# Main.net
KiCad netlist of a schematic drawn in EAGLE
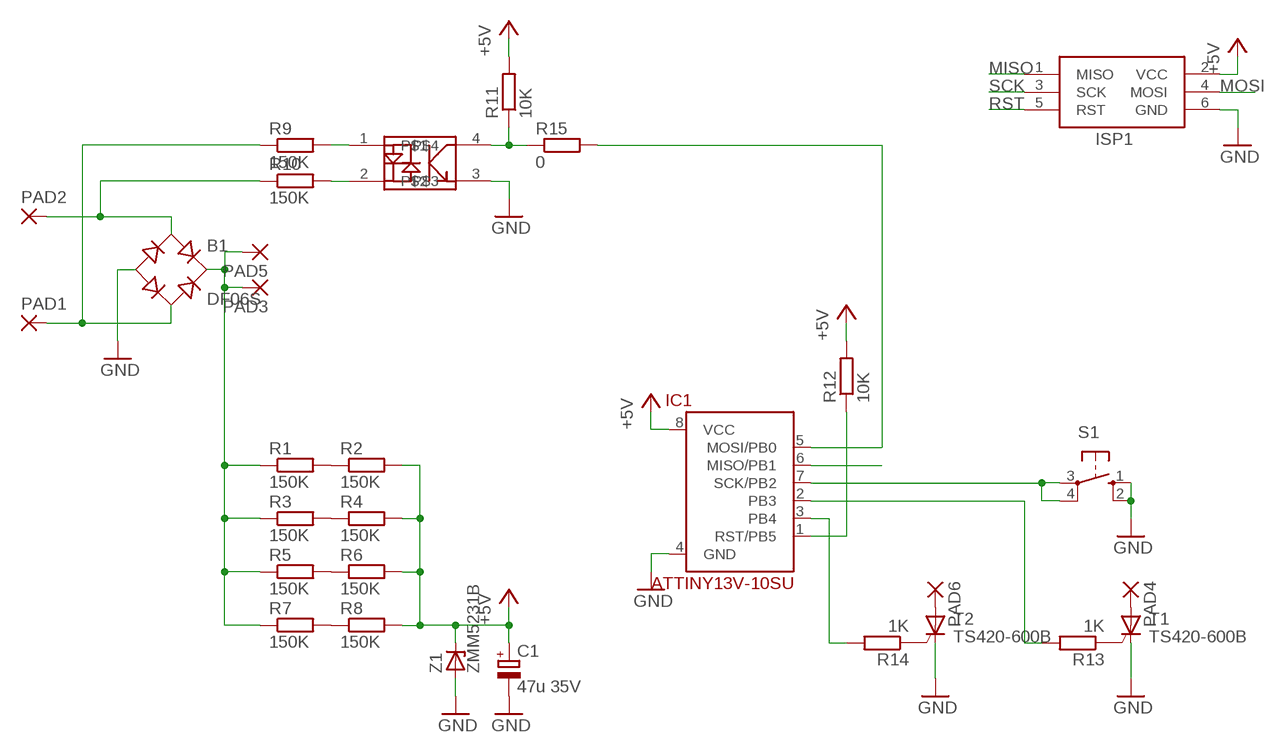
[diagram p0: schematic, sheet 1]

(export (version "E")
  (design (tool "Eeschema 10.0.6"))
  (components
    (comp (ref "B1")
      (value "DF06S")
      (footprint "eagle-import:DFS")
      (libsource (lib "eagle-import") (part "DFS06"))
    )
    (comp (ref "C1")
      (value "47u 35V")
      (footprint "eagle-import:CT7343")
      (libsource (lib "eagle-import") (part "CPOL-EUCT7343"))
    )
    (comp (ref "IC1")
      (value "ATTINY13V-10SU")
      (footprint "eagle-import:SOIC8")
      (libsource (lib "eagle-import") (part "ATTINY13V-10SU"))
    )
    (comp (ref "ISP1")
      (value "AVRISP-6")
      (footprint "eagle-import:AVRISP")
      (libsource (lib "eagle-import") (part "AVRISP-6"))
    )
    (comp (ref "PAD1")
      (value "SMD5")
      (footprint "eagle-import:SMD2,54-5,08")
      (libsource (lib "eagle-import") (part "SMD5"))
    )
    (comp (ref "PAD2")
      (value "SMD5")
      (footprint "eagle-import:SMD2,54-5,08")
      (libsource (lib "eagle-import") (part "SMD5"))
    )
    (comp (ref "PAD3")
      (value "SMD5")
      (footprint "eagle-import:SMD2,54-5,08")
      (libsource (lib "eagle-import") (part "SMD5"))
    )
    (comp (ref "PAD4")
      (value "SMD5")
      (footprint "eagle-import:SMD2,54-5,08")
      (libsource (lib "eagle-import") (part "SMD5"))
    )
    (comp (ref "PAD5")
      (value "SMD5")
      (footprint "eagle-import:SMD2,54-5,08")
      (libsource (lib "eagle-import") (part "SMD5"))
    )
    (comp (ref "PAD6")
      (value "SMD5")
      (footprint "eagle-import:SMD2,54-5,08")
      (libsource (lib "eagle-import") (part "SMD5"))
    )
    (comp (ref "R1")
      (value "150K")
      (footprint "eagle-import:R1206")
      (libsource (lib "eagle-import") (part "R_1206"))
    )
    (comp (ref "R2")
      (value "150K")
      (footprint "eagle-import:R1206")
      (libsource (lib "eagle-import") (part "R_1206"))
    )
    (comp (ref "R3")
      (value "150K")
      (footprint "eagle-import:R1206")
      (libsource (lib "eagle-import") (part "R_1206"))
    )
    (comp (ref "R4")
      (value "150K")
      (footprint "eagle-import:R1206")
      (libsource (lib "eagle-import") (part "R_1206"))
    )
    (comp (ref "R5")
      (value "150K")
      (footprint "eagle-import:R1206")
      (libsource (lib "eagle-import") (part "R_1206"))
    )
    (comp (ref "R6")
      (value "150K")
      (footprint "eagle-import:R1206")
      (libsource (lib "eagle-import") (part "R_1206"))
    )
    (comp (ref "R7")
      (value "150K")
      (footprint "eagle-import:R1206")
      (libsource (lib "eagle-import") (part "R_1206"))
    )
    (comp (ref "R8")
      (value "150K")
      (footprint "eagle-import:R1206")
      (libsource (lib "eagle-import") (part "R_1206"))
    )
    (comp (ref "R9")
      (value "150K")
      (footprint "eagle-import:R1206")
      (libsource (lib "eagle-import") (part "R_1206"))
    )
    (comp (ref "R10")
      (value "150K")
      (footprint "eagle-import:R1206")
      (libsource (lib "eagle-import") (part "R_1206"))
    )
    (comp (ref "R11")
      (value "10K")
      (footprint "eagle-import:R1206")
      (libsource (lib "eagle-import") (part "R_1206"))
    )
    (comp (ref "R12")
      (value "10K")
      (footprint "eagle-import:R1206")
      (libsource (lib "eagle-import") (part "R_1206"))
    )
    (comp (ref "R13")
      (value "1K")
      (footprint "eagle-import:R1206")
      (libsource (lib "eagle-import") (part "R_1206"))
    )
    (comp (ref "R14")
      (value "1K")
      (footprint "eagle-import:R1206")
      (libsource (lib "eagle-import") (part "R_1206"))
    )
    (comp (ref "R15")
      (value "0")
      (footprint "eagle-import:R0805")
      (libsource (lib "eagle-import") (part "R_0805"))
    )
    (comp (ref "S1")
      (value "10-XX")
      (footprint "eagle-import:B3F-10XX")
      (fields (field (name "MPN") "B3F-1000"))
      (libsource (lib "eagle-import") (part "10-XX"))
    )
    (comp (ref "T1")
      (value "TS420-600B")
      (footprint "eagle-import:DPAK")
      (libsource (lib "eagle-import") (part "THYRISTOR"))
    )
    (comp (ref "T2")
      (value "TS420-600B")
      (footprint "eagle-import:DPAK")
      (libsource (lib "eagle-import") (part "THYRISTOR"))
    )
    (comp (ref "U$1")
      (value "OPTO-EL3H4(TA)-VG")
      (footprint "eagle-import:SSOP4")
      (libsource (lib "eagle-import") (part "OPTO-EL3H4(TA)-VG"))
    )
    (comp (ref "Z1")
      (value "ZMM5231B")
      (footprint "eagle-import:MINIMELF")
      (libsource (lib "eagle-import") (part "ZENER_MINIMELF"))
    )
  )
  (nets
    (net (code "1") (name "+5V") (class "Default")
      (node (ref "C1") (pin "+") (pinfunction "+_+") (pintype "passive"))
      (node (ref "IC1") (pin "8") (pinfunction "VCC_8") (pintype "power_in"))
      (node (ref "ISP1") (pin "2") (pinfunction "VCC_2") (pintype "power_in"))
      (node (ref "R11") (pin "2") (pinfunction "2_2") (pintype "passive"))
      (node (ref "R12") (pin "2") (pinfunction "2_2") (pintype "passive"))
      (node (ref "R2") (pin "2") (pinfunction "2_2") (pintype "passive"))
      (node (ref "R4") (pin "2") (pinfunction "2_2") (pintype "passive"))
      (node (ref "R6") (pin "2") (pinfunction "2_2") (pintype "passive"))
      (node (ref "R8") (pin "2") (pinfunction "2_2") (pintype "passive"))
      (node (ref "Z1") (pin "C") (pinfunction "C_C") (pintype "passive"))
    )
    (net (code "2") (name "/MISO") (class "Default")
      (node (ref "IC1") (pin "6") (pinfunction "MISO/PB1_6") (pintype "bidirectional"))
      (node (ref "ISP1") (pin "1") (pinfunction "MISO_1") (pintype "input"))
    )
    (net (code "3") (name "/MOSI") (class "Default")
      (node (ref "IC1") (pin "5") (pinfunction "MOSI/PB0_5") (pintype "bidirectional"))
      (node (ref "ISP1") (pin "4") (pinfunction "MOSI_4") (pintype "output"))
      (node (ref "R15") (pin "2") (pinfunction "2_2") (pintype "passive"))
    )
    (net (code "4") (name "/RST") (class "Default")
      (node (ref "IC1") (pin "1") (pinfunction "RST/PB5_1") (pintype "bidirectional"))
      (node (ref "ISP1") (pin "5") (pinfunction "RST_5") (pintype "output"))
      (node (ref "R12") (pin "1") (pinfunction "1_1") (pintype "passive"))
    )
    (net (code "5") (name "/SCK") (class "Default")
      (node (ref "IC1") (pin "7") (pinfunction "SCK/PB2_7") (pintype "bidirectional"))
      (node (ref "ISP1") (pin "3") (pinfunction "SCK_3") (pintype "output"))
      (node (ref "S1") (pin "3") (pinfunction "P_3") (pintype "passive"))
      (node (ref "S1") (pin "4") (pinfunction "P1_4") (pintype "passive"))
    )
    (net (code "6") (name "GND") (class "Default")
      (node (ref "B1") (pin "-") (pinfunction "-_-") (pintype "passive"))
      (node (ref "C1") (pin "-") (pinfunction "-_-") (pintype "passive"))
      (node (ref "IC1") (pin "4") (pinfunction "GND_4") (pintype "power_in"))
      (node (ref "ISP1") (pin "6") (pinfunction "GND_6") (pintype "power_in"))
      (node (ref "S1") (pin "1") (pinfunction "S_1") (pintype "passive"))
      (node (ref "S1") (pin "2") (pinfunction "S1_2") (pintype "passive"))
      (node (ref "T1") (pin "G") (pinfunction "C_G") (pintype "passive"))
      (node (ref "T2") (pin "G") (pinfunction "C_G") (pintype "passive"))
      (node (ref "U$1") (pin "3") (pinfunction "P$3_3") (pintype "bidirectional"))
      (node (ref "Z1") (pin "A") (pinfunction "A_A") (pintype "passive"))
    )
    (net (code "7") (name "Net-(IC1-PB3)") (class "Default")
      (node (ref "IC1") (pin "2") (pinfunction "PB3_2") (pintype "bidirectional"))
      (node (ref "R13") (pin "2") (pinfunction "2_2") (pintype "passive"))
    )
    (net (code "8") (name "Net-(IC1-PB4)") (class "Default")
      (node (ref "IC1") (pin "3") (pinfunction "PB4_3") (pintype "bidirectional"))
      (node (ref "R14") (pin "2") (pinfunction "2_2") (pintype "passive"))
    )
    (net (code "9") (name "Net-(PAD1-P)") (class "Default")
      (node (ref "B1") (pin "AC2") (pinfunction "AC2_AC2") (pintype "passive"))
      (node (ref "PAD1") (pin "1") (pinfunction "P_1") (pintype "passive"))
      (node (ref "R9") (pin "1") (pinfunction "1_1") (pintype "passive"))
    )
    (net (code "10") (name "Net-(PAD2-P)") (class "Default")
      (node (ref "B1") (pin "AC1") (pinfunction "AC1_AC1") (pintype "passive"))
      (node (ref "PAD2") (pin "1") (pinfunction "P_1") (pintype "passive"))
      (node (ref "R10") (pin "1") (pinfunction "1_1") (pintype "passive"))
    )
    (net (code "11") (name "Net-(PAD3-P)") (class "Default")
      (node (ref "B1") (pin "+") (pinfunction "+_+") (pintype "passive"))
      (node (ref "PAD3") (pin "1") (pinfunction "P_1") (pintype "passive"))
      (node (ref "PAD5") (pin "1") (pinfunction "P_1") (pintype "passive"))
      (node (ref "R1") (pin "1") (pinfunction "1_1") (pintype "passive"))
      (node (ref "R3") (pin "1") (pinfunction "1_1") (pintype "passive"))
      (node (ref "R5") (pin "1") (pinfunction "1_1") (pintype "passive"))
      (node (ref "R7") (pin "1") (pinfunction "1_1") (pintype "passive"))
    )
    (net (code "12") (name "Net-(PAD4-P)") (class "Default")
      (node (ref "PAD4") (pin "1") (pinfunction "P_1") (pintype "passive"))
      (node (ref "T1") (pin "D") (pinfunction "A_D") (pintype "passive"))
    )
    (net (code "13") (name "Net-(PAD6-P)") (class "Default")
      (node (ref "PAD6") (pin "1") (pinfunction "P_1") (pintype "passive"))
      (node (ref "T2") (pin "D") (pinfunction "A_D") (pintype "passive"))
    )
    (net (code "14") (name "Net-(R1-Pad2)") (class "Default")
      (node (ref "R1") (pin "2") (pinfunction "2_2") (pintype "passive"))
      (node (ref "R2") (pin "1") (pinfunction "1_1") (pintype "passive"))
    )
    (net (code "15") (name "Net-(R3-Pad2)") (class "Default")
      (node (ref "R3") (pin "2") (pinfunction "2_2") (pintype "passive"))
      (node (ref "R4") (pin "1") (pinfunction "1_1") (pintype "passive"))
    )
    (net (code "16") (name "Net-(R5-Pad2)") (class "Default")
      (node (ref "R5") (pin "2") (pinfunction "2_2") (pintype "passive"))
      (node (ref "R6") (pin "1") (pinfunction "1_1") (pintype "passive"))
    )
    (net (code "17") (name "Net-(R7-Pad2)") (class "Default")
      (node (ref "R7") (pin "2") (pinfunction "2_2") (pintype "passive"))
      (node (ref "R8") (pin "1") (pinfunction "1_1") (pintype "passive"))
    )
    (net (code "18") (name "Net-(T1-G)") (class "Default")
      (node (ref "R13") (pin "1") (pinfunction "1_1") (pintype "passive"))
      (node (ref "T1") (pin "S") (pinfunction "G_S") (pintype "passive"))
    )
    (net (code "19") (name "Net-(T2-G)") (class "Default")
      (node (ref "R14") (pin "1") (pinfunction "1_1") (pintype "passive"))
      (node (ref "T2") (pin "S") (pinfunction "G_S") (pintype "passive"))
    )
    (net (code "20") (name "Net-(U$1-P$1)") (class "Default")
      (node (ref "R9") (pin "2") (pinfunction "2_2") (pintype "passive"))
      (node (ref "U$1") (pin "1") (pinfunction "P$1_1") (pintype "bidirectional"))
    )
    (net (code "21") (name "Net-(U$1-P$2)") (class "Default")
      (node (ref "R10") (pin "2") (pinfunction "2_2") (pintype "passive"))
      (node (ref "U$1") (pin "2") (pinfunction "P$2_2") (pintype "bidirectional"))
    )
    (net (code "22") (name "Net-(U$1-P$4)") (class "Default")
      (node (ref "R11") (pin "1") (pinfunction "1_1") (pintype "passive"))
      (node (ref "R15") (pin "1") (pinfunction "1_1") (pintype "passive"))
      (node (ref "U$1") (pin "4") (pinfunction "P$4_4") (pintype "bidirectional"))
    )
  )
)
